# COMMUNICATION.net
KiCad netlist of a schematic drawn in Altium Designer
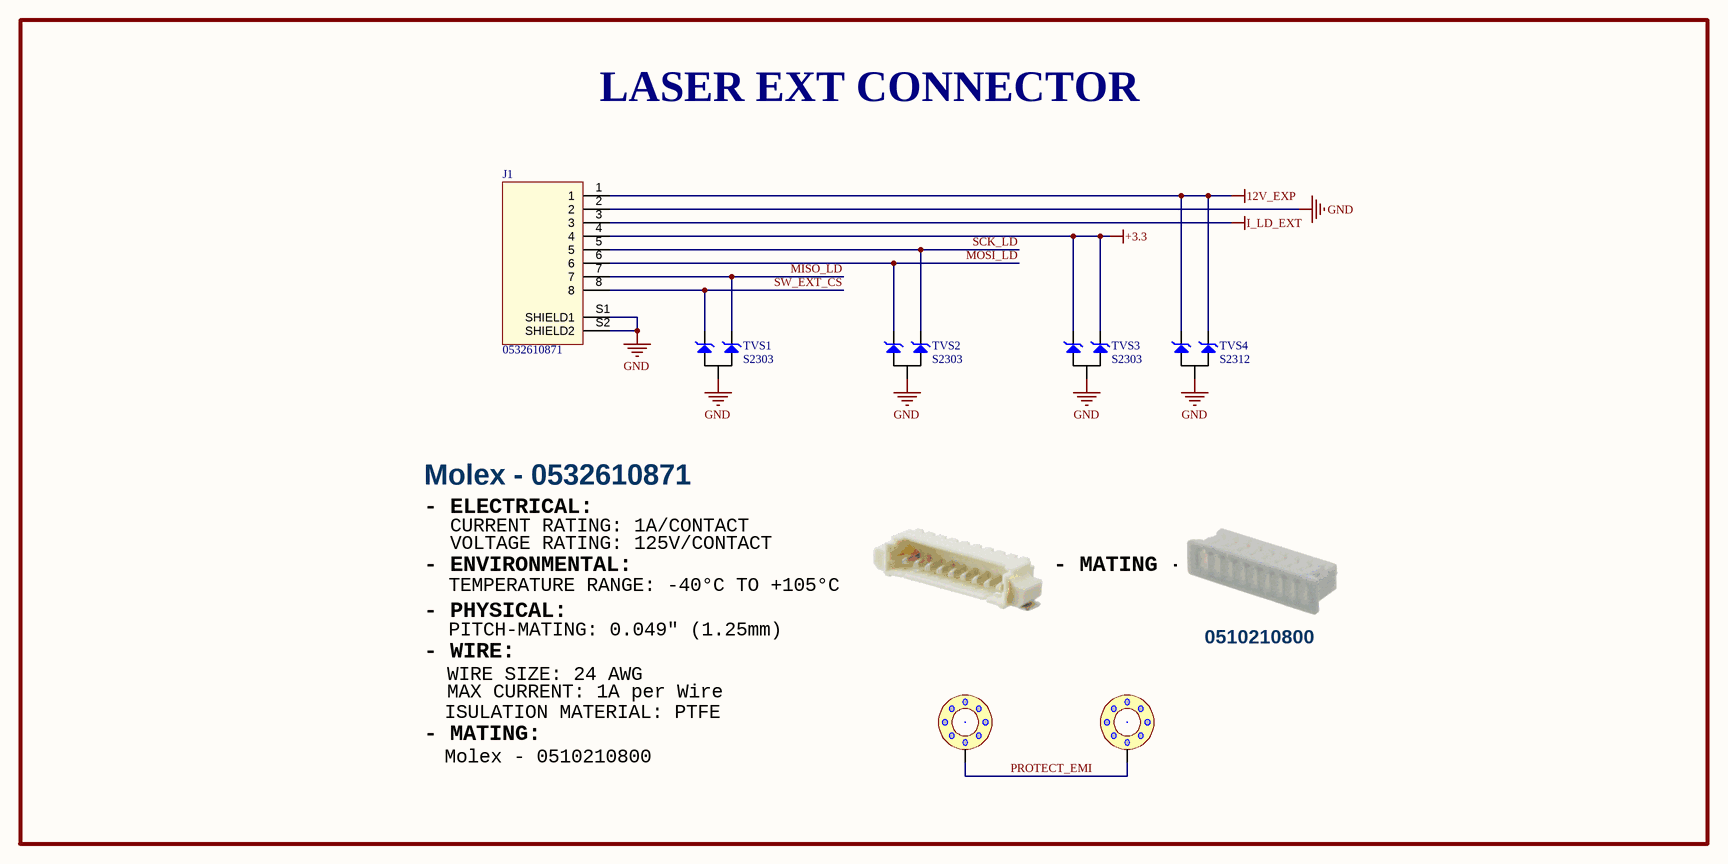
[diagram p0: COMMUNICATION.SchDoc]

(export (version "E")
  (design (tool "Eeschema 10.0.6"))
  (components
    (comp (ref "Hole1") (value "Hole") (footprint "Hole space") (libsource (lib "Library") (part "Hole")))
    (comp (ref "Hole2") (value "Hole") (footprint "Hole space") (libsource (lib "Library") (part "Hole")))
    (comp (ref "J1")
      (value "0532610871")
      (footprint "0532610871")
      (description "CONN HEADER SMD R/A 8POS 1.25MM")
      (libsource (lib "Library") (part "Header8 - Shield"))
    )
    (comp (ref "TVS1")
      (value "S2303")
      (footprint "SOT23-123")
      (description "TVS DIODE 3.3VWM 8VC SOT233")
      (libsource (lib "Library") (part "S2303"))
    )
    (comp (ref "TVS2")
      (value "S2303")
      (footprint "SOT23-123")
      (description "TVS DIODE 3.3VWM 8VC SOT233")
      (libsource (lib "Library") (part "S2303"))
    )
    (comp (ref "TVS3")
      (value "S2303")
      (footprint "SOT23-123")
      (description "TVS DIODE 3.3VWM 8VC SOT233")
      (libsource (lib "Library") (part "S2303"))
    )
    (comp (ref "TVS4")
      (value "S2312")
      (footprint "SOT23-123")
      (description "TVS DIODE 12VWM 19VC SOT233")
      (libsource (lib "Library") (part "S2315"))
    )
  )
  (nets
    (net (code "1") (name "+3.3") (class "Default")
      (node (ref "J1") (pin "4") (pinfunction "4_4") (pintype "passive"))
      (node (ref "TVS3") (pin "1") (pintype "passive"))
      (node (ref "TVS3") (pin "3") (pintype "passive"))
    )
    (net (code "2") (name "/MISO_LD") (class "Default")
      (node (ref "J1") (pin "7") (pinfunction "7_7") (pintype "passive"))
      (node (ref "TVS1") (pin "1") (pintype "passive"))
    )
    (net (code "3") (name "/MOSI_LD") (class "Default")
      (node (ref "J1") (pin "6") (pinfunction "6_6") (pintype "passive"))
      (node (ref "TVS2") (pin "3") (pintype "passive"))
    )
    (net (code "4") (name "/PROTECT_EMI") (class "Default")
      (node (ref "Hole1") (pin "1") (pinfunction "1_1") (pintype "passive"))
      (node (ref "Hole2") (pin "1") (pinfunction "1_1") (pintype "passive"))
    )
    (net (code "5") (name "/SCK_LD") (class "Default")
      (node (ref "J1") (pin "5") (pinfunction "5_5") (pintype "passive"))
      (node (ref "TVS2") (pin "1") (pintype "passive"))
    )
    (net (code "6") (name "/SW_EXT_CS") (class "Default")
      (node (ref "J1") (pin "8") (pinfunction "8_8") (pintype "passive"))
      (node (ref "TVS1") (pin "3") (pintype "passive"))
    )
    (net (code "7") (name "12V_EXP") (class "Default")
      (node (ref "J1") (pin "1") (pinfunction "1_1") (pintype "passive"))
      (node (ref "TVS4") (pin "1") (pintype "passive"))
      (node (ref "TVS4") (pin "3") (pintype "passive"))
    )
    (net (code "8") (name "GND") (class "Default")
      (node (ref "J1") (pin "2") (pinfunction "2_2") (pintype "passive"))
      (node (ref "J1") (pin "S1") (pinfunction "SHIELD1_S1") (pintype "passive"))
      (node (ref "J1") (pin "S2") (pinfunction "SHIELD2_S2") (pintype "passive"))
      (node (ref "TVS1") (pin "2") (pintype "passive"))
      (node (ref "TVS2") (pin "2") (pintype "passive"))
      (node (ref "TVS3") (pin "2") (pintype "passive"))
      (node (ref "TVS4") (pin "2") (pintype "passive"))
    )
    (net (code "9") (name "I_LD_EXT") (class "Default")
      (node (ref "J1") (pin "3") (pinfunction "3_3") (pintype "passive"))
    )
  )
)
